# BoomClock.net
KiCad netlist of a schematic drawn in Altium Designer
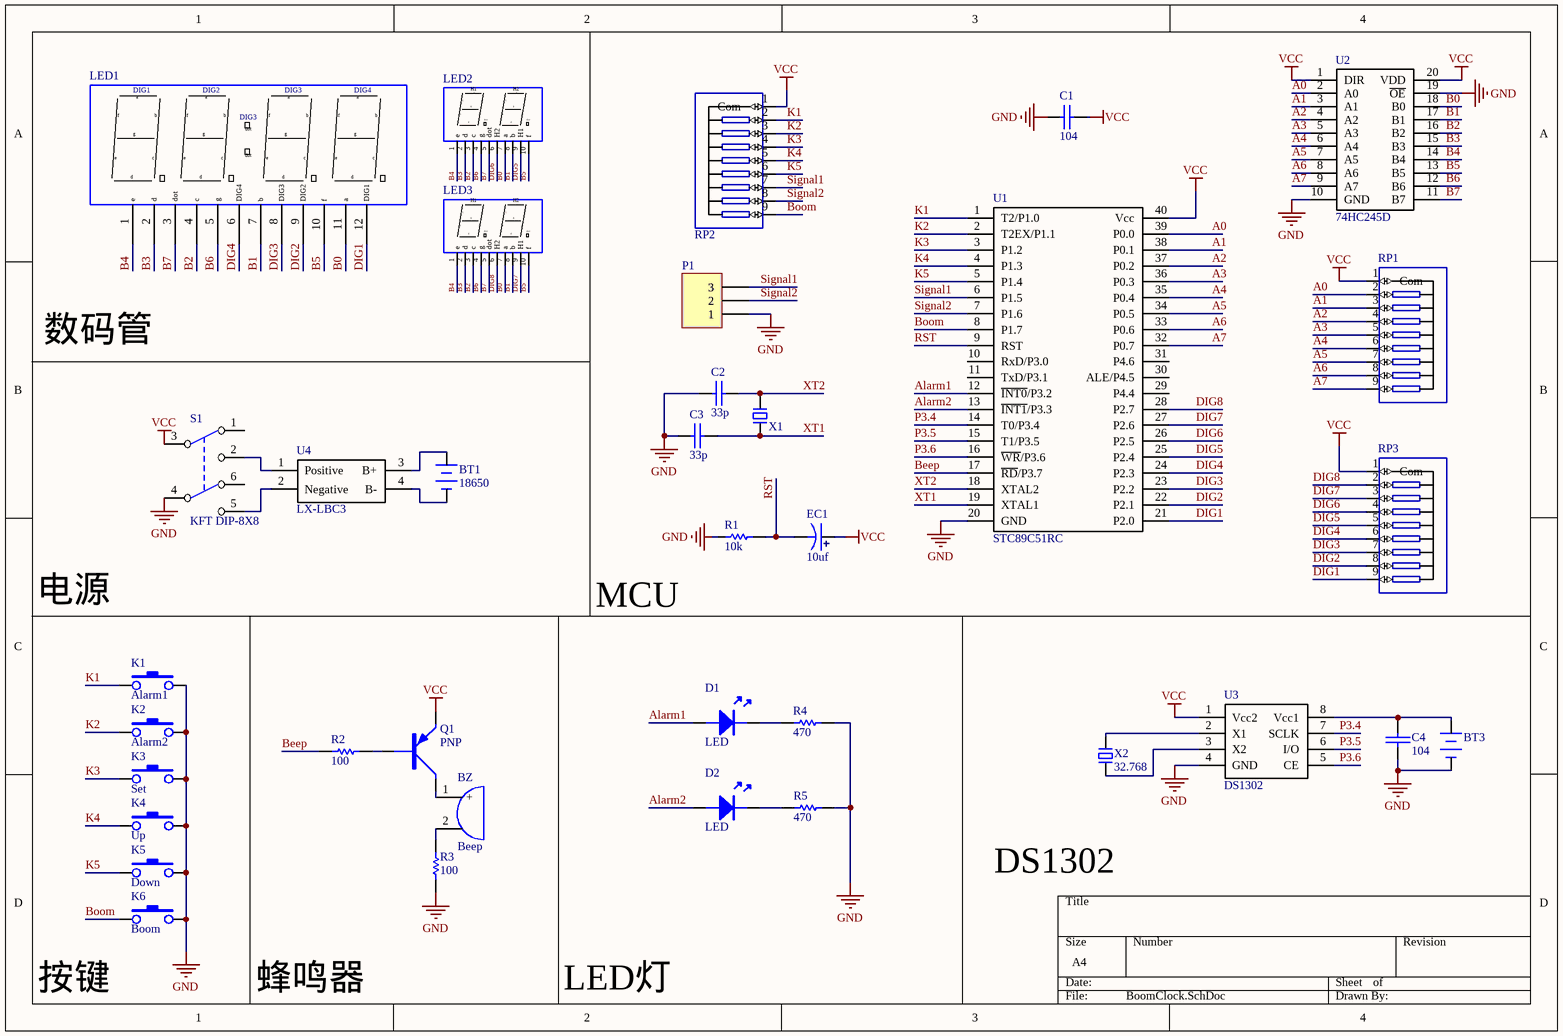
[diagram p0: BoomClock.SchDoc]

(export (version "E")
  (design (tool "Eeschema 10.0.6"))
  (components
    (comp (ref "BT1")
      (value "18650")
      (footprint "Battery_18650")
      (description "电池")
      (libsource (lib "BoomClock") (part "Battery"))
    )
    (comp (ref "BT3")
      (value "Battery")
      (footprint "Battery_CR2032")
      (description "电池")
      (libsource (lib "BoomClock") (part "Battery"))
    )
    (comp (ref "BZ")
      (value "Beep")
      (footprint "Beep")
      (description "蜂鸣器")
      (libsource (lib "BoomClock") (part "Beep"))
    )
    (comp (ref "C1")
      (value "104")
      (footprint "RAD-0.1")
      (description "无极性电容")
      (libsource (lib "BoomClock") (part "CAP"))
    )
    (comp (ref "C2")
      (value "33p")
      (footprint "RAD-0.1")
      (description "无极性电容")
      (libsource (lib "BoomClock") (part "CAP"))
    )
    (comp (ref "C3")
      (value "33p")
      (footprint "RAD-0.1")
      (description "无极性电容")
      (libsource (lib "BoomClock") (part "CAP"))
    )
    (comp (ref "C4")
      (value "104")
      (footprint "RAD-0.1")
      (description "无极性电容")
      (libsource (lib "BoomClock") (part "CAP"))
    )
    (comp (ref "D1") (value "LED") (footprint "LED5-YEL") (libsource (lib "BoomClock") (part "LED")))
    (comp (ref "D2") (value "LED") (footprint "LED5-BLUE") (libsource (lib "BoomClock") (part "LED")))
    (comp (ref "EC1")
      (value "10uf")
      (footprint "DIP-EC1.5X4X8")
      (description "直插电解电容")
      (libsource (lib "BoomClock") (part "DIP_ECAP"))
    )
    (comp (ref "K1")
      (value "Alarm1")
      (footprint "DIP-6X6X5")
      (description "按动开关")
      (libsource (lib "BoomClock") (part "KEY"))
    )
    (comp (ref "K2")
      (value "Alarm2")
      (footprint "DIP-6X6X5")
      (description "按动开关")
      (libsource (lib "BoomClock") (part "KEY"))
    )
    (comp (ref "K3")
      (value "Set")
      (footprint "DIP-6X6X5")
      (description "按动开关")
      (libsource (lib "BoomClock") (part "KEY"))
    )
    (comp (ref "K4")
      (value "Up")
      (footprint "DIP-6X6X5")
      (description "按动开关")
      (libsource (lib "BoomClock") (part "KEY"))
    )
    (comp (ref "K5")
      (value "Down")
      (footprint "DIP-6X6X5")
      (description "按动开关")
      (libsource (lib "BoomClock") (part "KEY"))
    )
    (comp (ref "K6")
      (value "Boom")
      (footprint "DIP-12X12X8")
      (description "按动开关")
      (libsource (lib "BoomClock") (part "KEY"))
    )
    (comp (ref "LED1")
      (value "Digital_4_time")
      (footprint "Digital_4_time")
      (description "四位时间数码管")
      (libsource (lib "BoomClock") (part "Digital_4_time"))
    )
    (comp (ref "LED2")
      (value "Digital_2")
      (footprint "Digital_2")
      (description "二位数码管")
      (libsource (lib "BoomClock") (part "Digital_2"))
    )
    (comp (ref "LED3")
      (value "Digital_2")
      (footprint "Digital_2")
      (description "二位数码管")
      (libsource (lib "BoomClock") (part "Digital_2"))
    )
    (comp (ref "P1")
      (value "Header 3")
      (footprint "HDR1X3")
      (description "Header, 3-Pin")
      (fields (field (name "PUBLISHER") "Altium Limited"))
      (libsource (lib "Miscellaneous Connectors") (part "Header 3"))
    )
    (comp (ref "Q1")
      (value "PNP")
      (footprint "SOT-23")
      (description "PNP三极管")
      (libsource (lib "BoomClock") (part "PNP"))
    )
    (comp (ref "R1")
      (value "10k")
      (footprint "0805R")
      (description "电阻")
      (libsource (lib "BoomClock") (part "RES"))
    )
    (comp (ref "R2")
      (value "100")
      (footprint "0805R")
      (description "电阻")
      (libsource (lib "BoomClock") (part "RES"))
    )
    (comp (ref "R3")
      (value "100")
      (footprint "0805R")
      (description "电阻")
      (libsource (lib "BoomClock") (part "RES"))
    )
    (comp (ref "R4")
      (value "470")
      (footprint "AXIAL0.4")
      (description "电阻")
      (libsource (lib "BoomClock") (part "RES"))
    )
    (comp (ref "R5")
      (value "470")
      (footprint "AXIAL0.4")
      (description "电阻")
      (libsource (lib "BoomClock") (part "RES"))
    )
    (comp (ref "RP1")
      (value "RES_PACK9")
      (footprint "A09R")
      (description "排阻")
      (libsource (lib "BoomClock") (part "RES_PACK9"))
    )
    (comp (ref "RP2")
      (value "RES_PACK9")
      (footprint "A09R")
      (description "排阻")
      (libsource (lib "BoomClock") (part "RES_PACK9"))
    )
    (comp (ref "RP3")
      (value "RES_PACK9")
      (footprint "A09R")
      (description "排阻")
      (libsource (lib "BoomClock") (part "RES_PACK9"))
    )
    (comp (ref "S1")
      (value "KFT DIP-8X8")
      (footprint "KFT DIP-8X8")
      (libsource (lib "BoomClock") (part "KFT DIP-8X8"))
    )
    (comp (ref "U1")
      (value "STC89C51RC")
      (footprint "DIP40")
      (libsource (lib "BoomClock") (part "STC89C51RC"))
    )
    (comp (ref "U2") (value "74HC245D") (footprint "SOP20") (libsource (lib "BoomClock") (part "74HC245D")))
    (comp (ref "U3") (value "DS1302") (footprint "DIP8") (libsource (lib "BoomClock") (part "DS1302")))
    (comp (ref "U4")
      (value "LX-LBC3")
      (footprint "LX-LBC3")
      (description "电源模块")
      (libsource (lib "BoomClock") (part "LX-LBC3"))
    )
    (comp (ref "X1")
      (value "XTAL-2P")
      (footprint "OSC HC-49S")
      (description "2脚无源脚晶振")
      (libsource (lib "BoomClock") (part "XTAL-2P"))
    )
    (comp (ref "X2")
      (value "32.768")
      (footprint "OSC-2x6-WI-A")
      (description "2脚无源脚晶振")
      (libsource (lib "BoomClock") (part "XTAL-2P"))
    )
  )
  (nets
    (net (code "1") (name "/A0") (class "Default")
      (node (ref "RP1") (pin "2") (pinfunction "2_2") (pintype "bidirectional"))
      (node (ref "U1") (pin "39") (pinfunction "P0.0_39") (pintype "passive"))
      (node (ref "U2") (pin "2") (pinfunction "A0_2") (pintype "passive"))
    )
    (net (code "2") (name "/A1") (class "Default")
      (node (ref "RP1") (pin "3") (pinfunction "3_3") (pintype "bidirectional"))
      (node (ref "U1") (pin "38") (pinfunction "P0.1_38") (pintype "passive"))
      (node (ref "U2") (pin "3") (pinfunction "A1_3") (pintype "passive"))
    )
    (net (code "3") (name "/A2") (class "Default")
      (node (ref "RP1") (pin "4") (pinfunction "4_4") (pintype "bidirectional"))
      (node (ref "U1") (pin "37") (pinfunction "P0.2_37") (pintype "passive"))
      (node (ref "U2") (pin "4") (pinfunction "A2_4") (pintype "passive"))
    )
    (net (code "4") (name "/A3") (class "Default")
      (node (ref "RP1") (pin "5") (pinfunction "5_5") (pintype "bidirectional"))
      (node (ref "U1") (pin "36") (pinfunction "P0.3_36") (pintype "passive"))
      (node (ref "U2") (pin "5") (pinfunction "A3_5") (pintype "passive"))
    )
    (net (code "5") (name "/A4") (class "Default")
      (node (ref "RP1") (pin "6") (pinfunction "6_6") (pintype "bidirectional"))
      (node (ref "U1") (pin "35") (pinfunction "P0.4_35") (pintype "passive"))
      (node (ref "U2") (pin "6") (pinfunction "A4_6") (pintype "passive"))
    )
    (net (code "6") (name "/A5") (class "Default")
      (node (ref "RP1") (pin "7") (pinfunction "7_7") (pintype "bidirectional"))
      (node (ref "U1") (pin "34") (pinfunction "P0.5_34") (pintype "passive"))
      (node (ref "U2") (pin "7") (pinfunction "A5_7") (pintype "passive"))
    )
    (net (code "7") (name "/A6") (class "Default")
      (node (ref "RP1") (pin "8") (pinfunction "8_8") (pintype "bidirectional"))
      (node (ref "U1") (pin "33") (pinfunction "P0.6_33") (pintype "passive"))
      (node (ref "U2") (pin "8") (pinfunction "A6_8") (pintype "passive"))
    )
    (net (code "8") (name "/A7") (class "Default")
      (node (ref "RP1") (pin "9") (pinfunction "9_9") (pintype "bidirectional"))
      (node (ref "U1") (pin "32") (pinfunction "P0.7_32") (pintype "passive"))
      (node (ref "U2") (pin "9") (pinfunction "A7_9") (pintype "passive"))
    )
    (net (code "9") (name "/Alarm1") (class "Default")
      (node (ref "D1") (pin "A") (pinfunction "A_A") (pintype "passive"))
      (node (ref "U1") (pin "12") (pinfunction "~{INT0}/P3.2_12") (pintype "passive"))
    )
    (net (code "10") (name "/Alarm2") (class "Default")
      (node (ref "D2") (pin "A") (pinfunction "A_A") (pintype "passive"))
      (node (ref "U1") (pin "13") (pinfunction "~{INT1}/P3.3_13") (pintype "passive"))
    )
    (net (code "11") (name "/B0") (class "Default")
      (node (ref "LED1") (pin "11") (pinfunction "a_11") (pintype "passive"))
      (node (ref "LED2") (pin "7") (pinfunction "a_7") (pintype "passive"))
      (node (ref "LED3") (pin "7") (pinfunction "a_7") (pintype "passive"))
      (node (ref "U2") (pin "18") (pinfunction "B0_18") (pintype "passive"))
    )
    (net (code "12") (name "/B1") (class "Default")
      (node (ref "LED1") (pin "7") (pinfunction "b_7") (pintype "passive"))
      (node (ref "LED2") (pin "8") (pinfunction "b_8") (pintype "passive"))
      (node (ref "LED3") (pin "8") (pinfunction "b_8") (pintype "passive"))
      (node (ref "U2") (pin "17") (pinfunction "B1_17") (pintype "passive"))
    )
    (net (code "13") (name "/B2") (class "Default")
      (node (ref "LED1") (pin "4") (pinfunction "c_4") (pintype "passive"))
      (node (ref "LED2") (pin "3") (pinfunction "c_3") (pintype "passive"))
      (node (ref "LED3") (pin "3") (pinfunction "c_3") (pintype "passive"))
      (node (ref "U2") (pin "16") (pinfunction "B2_16") (pintype "passive"))
    )
    (net (code "14") (name "/B3") (class "Default")
      (node (ref "LED1") (pin "2") (pinfunction "d_2") (pintype "passive"))
      (node (ref "LED2") (pin "2") (pinfunction "d_2") (pintype "passive"))
      (node (ref "LED3") (pin "2") (pinfunction "d_2") (pintype "passive"))
      (node (ref "U2") (pin "15") (pinfunction "B3_15") (pintype "passive"))
    )
    (net (code "15") (name "/B4") (class "Default")
      (node (ref "LED1") (pin "1") (pinfunction "e_1") (pintype "passive"))
      (node (ref "LED2") (pin "1") (pinfunction "e_1") (pintype "passive"))
      (node (ref "LED3") (pin "1") (pinfunction "e_1") (pintype "passive"))
      (node (ref "U2") (pin "14") (pinfunction "B4_14") (pintype "passive"))
    )
    (net (code "16") (name "/B5") (class "Default")
      (node (ref "LED1") (pin "10") (pinfunction "f_10") (pintype "passive"))
      (node (ref "LED2") (pin "10") (pinfunction "f_10") (pintype "passive"))
      (node (ref "LED3") (pin "10") (pinfunction "f_10") (pintype "passive"))
      (node (ref "U2") (pin "13") (pinfunction "B5_13") (pintype "passive"))
    )
    (net (code "17") (name "/B6") (class "Default")
      (node (ref "LED1") (pin "5") (pinfunction "g_5") (pintype "passive"))
      (node (ref "LED2") (pin "4") (pinfunction "g_4") (pintype "passive"))
      (node (ref "LED3") (pin "4") (pinfunction "g_4") (pintype "passive"))
      (node (ref "U2") (pin "12") (pinfunction "B6_12") (pintype "passive"))
    )
    (net (code "18") (name "/B7") (class "Default")
      (node (ref "LED1") (pin "3") (pinfunction "dot_3") (pintype "passive"))
      (node (ref "LED2") (pin "5") (pinfunction "dot_5") (pintype "passive"))
      (node (ref "LED3") (pin "5") (pinfunction "dot_5") (pintype "passive"))
      (node (ref "U2") (pin "11") (pinfunction "B7_11") (pintype "passive"))
    )
    (net (code "19") (name "/Beep") (class "Default")
      (node (ref "R2") (pin "1") (pinfunction "1_1") (pintype "passive"))
      (node (ref "U1") (pin "17") (pinfunction "~{RD}/P3.7_17") (pintype "passive"))
    )
    (net (code "20") (name "/Boom") (class "Default")
      (node (ref "K6") (pin "1") (pinfunction "1_1") (pintype "passive"))
      (node (ref "RP2") (pin "9") (pinfunction "9_9") (pintype "bidirectional"))
      (node (ref "U1") (pin "8") (pinfunction "P1.7_8") (pintype "passive"))
    )
    (net (code "21") (name "/DIG1") (class "Default")
      (node (ref "LED1") (pin "12") (pinfunction "DIG1_12") (pintype "passive"))
      (node (ref "RP3") (pin "9") (pinfunction "9_9") (pintype "bidirectional"))
      (node (ref "U1") (pin "21") (pinfunction "P2.0_21") (pintype "passive"))
    )
    (net (code "22") (name "/DIG2") (class "Default")
      (node (ref "LED1") (pin "9") (pinfunction "DIG2_9") (pintype "passive"))
      (node (ref "RP3") (pin "8") (pinfunction "8_8") (pintype "bidirectional"))
      (node (ref "U1") (pin "22") (pinfunction "P2.1_22") (pintype "passive"))
    )
    (net (code "23") (name "/DIG3") (class "Default")
      (node (ref "LED1") (pin "8") (pinfunction "DIG3_8") (pintype "passive"))
      (node (ref "RP3") (pin "7") (pinfunction "7_7") (pintype "bidirectional"))
      (node (ref "U1") (pin "23") (pinfunction "P2.2_23") (pintype "passive"))
    )
    (net (code "24") (name "/DIG4") (class "Default")
      (node (ref "LED1") (pin "6") (pinfunction "DIG4_6") (pintype "passive"))
      (node (ref "RP3") (pin "6") (pinfunction "6_6") (pintype "bidirectional"))
      (node (ref "U1") (pin "24") (pinfunction "P2.3_24") (pintype "passive"))
    )
    (net (code "25") (name "/DIG5") (class "Default")
      (node (ref "LED2") (pin "9") (pinfunction "H1_9") (pintype "passive"))
      (node (ref "RP3") (pin "5") (pinfunction "5_5") (pintype "bidirectional"))
      (node (ref "U1") (pin "25") (pinfunction "P2.4_25") (pintype "passive"))
    )
    (net (code "26") (name "/DIG6") (class "Default")
      (node (ref "LED2") (pin "6") (pinfunction "H2_6") (pintype "passive"))
      (node (ref "RP3") (pin "4") (pinfunction "4_4") (pintype "bidirectional"))
      (node (ref "U1") (pin "26") (pinfunction "P2.5_26") (pintype "passive"))
    )
    (net (code "27") (name "/DIG7") (class "Default")
      (node (ref "LED3") (pin "9") (pinfunction "H1_9") (pintype "passive"))
      (node (ref "RP3") (pin "3") (pinfunction "3_3") (pintype "bidirectional"))
      (node (ref "U1") (pin "27") (pinfunction "P2.6_27") (pintype "passive"))
    )
    (net (code "28") (name "/DIG8") (class "Default")
      (node (ref "LED3") (pin "6") (pinfunction "H2_6") (pintype "passive"))
      (node (ref "RP3") (pin "2") (pinfunction "2_2") (pintype "bidirectional"))
      (node (ref "U1") (pin "28") (pinfunction "P2.7_28") (pintype "passive"))
    )
    (net (code "29") (name "/K1") (class "Default")
      (node (ref "K1") (pin "1") (pinfunction "1_1") (pintype "passive"))
      (node (ref "RP2") (pin "2") (pinfunction "2_2") (pintype "bidirectional"))
      (node (ref "U1") (pin "1") (pinfunction "T2/P1.0_1") (pintype "passive"))
    )
    (net (code "30") (name "/K2") (class "Default")
      (node (ref "K2") (pin "1") (pinfunction "1_1") (pintype "passive"))
      (node (ref "RP2") (pin "3") (pinfunction "3_3") (pintype "bidirectional"))
      (node (ref "U1") (pin "2") (pinfunction "T2EX/P1.1_2") (pintype "passive"))
    )
    (net (code "31") (name "/K3") (class "Default")
      (node (ref "K3") (pin "1") (pinfunction "1_1") (pintype "passive"))
      (node (ref "RP2") (pin "4") (pinfunction "4_4") (pintype "bidirectional"))
      (node (ref "U1") (pin "3") (pinfunction "P1.2_3") (pintype "passive"))
    )
    (net (code "32") (name "/K4") (class "Default")
      (node (ref "K4") (pin "1") (pinfunction "1_1") (pintype "passive"))
      (node (ref "RP2") (pin "5") (pinfunction "5_5") (pintype "bidirectional"))
      (node (ref "U1") (pin "4") (pinfunction "P1.3_4") (pintype "passive"))
    )
    (net (code "33") (name "/K5") (class "Default")
      (node (ref "K5") (pin "1") (pinfunction "1_1") (pintype "passive"))
      (node (ref "RP2") (pin "6") (pinfunction "6_6") (pintype "bidirectional"))
      (node (ref "U1") (pin "5") (pinfunction "P1.4_5") (pintype "passive"))
    )
    (net (code "34") (name "/P3.4") (class "Default")
      (node (ref "U1") (pin "14") (pinfunction "T0/P3.4_14") (pintype "passive"))
      (node (ref "U3") (pin "7") (pinfunction "SCLK_7") (pintype "passive"))
    )
    (net (code "35") (name "/P3.5") (class "Default")
      (node (ref "U1") (pin "15") (pinfunction "T1/P3.5_15") (pintype "passive"))
      (node (ref "U3") (pin "6") (pinfunction "I/O_6") (pintype "passive"))
    )
    (net (code "36") (name "/P3.6") (class "Default")
      (node (ref "U1") (pin "16") (pinfunction "~{WR}/P3.6_16") (pintype "passive"))
      (node (ref "U3") (pin "5") (pinfunction "CE_5") (pintype "passive"))
    )
    (net (code "37") (name "/RST") (class "Default")
      (node (ref "EC1") (pin "2") (pinfunction "2_2") (pintype "passive"))
      (node (ref "R1") (pin "2") (pinfunction "2_2") (pintype "passive"))
      (node (ref "U1") (pin "9") (pinfunction "RST_9") (pintype "passive"))
    )
    (net (code "38") (name "/Signal1") (class "Default")
      (node (ref "P1") (pin "3") (pinfunction "3_3") (pintype "passive"))
      (node (ref "RP2") (pin "7") (pinfunction "7_7") (pintype "bidirectional"))
      (node (ref "U1") (pin "6") (pinfunction "P1.5_6") (pintype "passive"))
    )
    (net (code "39") (name "/Signal2") (class "Default")
      (node (ref "P1") (pin "2") (pinfunction "2_2") (pintype "passive"))
      (node (ref "RP2") (pin "8") (pinfunction "8_8") (pintype "bidirectional"))
      (node (ref "U1") (pin "7") (pinfunction "P1.6_7") (pintype "passive"))
    )
    (net (code "40") (name "/XT1") (class "Default")
      (node (ref "C3") (pin "2") (pinfunction "2_2") (pintype "passive"))
      (node (ref "U1") (pin "19") (pinfunction "XTAL1_19") (pintype "passive"))
      (node (ref "X1") (pin "1") (pinfunction "1_1") (pintype "passive"))
    )
    (net (code "41") (name "/XT2") (class "Default")
      (node (ref "C2") (pin "2") (pinfunction "2_2") (pintype "passive"))
      (node (ref "U1") (pin "18") (pinfunction "XTAL2_18") (pintype "passive"))
      (node (ref "X1") (pin "2") (pinfunction "2_2") (pintype "passive"))
    )
    (net (code "42") (name "GND") (class "Default")
      (node (ref "BT3") (pin "2") (pinfunction "Negative_2") (pintype "passive"))
      (node (ref "C1") (pin "1") (pinfunction "1_1") (pintype "passive"))
      (node (ref "C2") (pin "1") (pinfunction "1_1") (pintype "passive"))
      (node (ref "C3") (pin "1") (pinfunction "1_1") (pintype "passive"))
      (node (ref "C4") (pin "1") (pinfunction "1_1") (pintype "passive"))
      (node (ref "K1") (pin "2") (pinfunction "2_2") (pintype "passive"))
      (node (ref "K2") (pin "2") (pinfunction "2_2") (pintype "passive"))
      (node (ref "K3") (pin "2") (pinfunction "2_2") (pintype "passive"))
      (node (ref "K4") (pin "2") (pinfunction "2_2") (pintype "passive"))
      (node (ref "K5") (pin "2") (pinfunction "2_2") (pintype "passive"))
      (node (ref "K6") (pin "2") (pinfunction "2_2") (pintype "passive"))
      (node (ref "P1") (pin "1") (pinfunction "1_1") (pintype "passive"))
      (node (ref "R1") (pin "1") (pinfunction "1_1") (pintype "passive"))
      (node (ref "R3") (pin "1") (pinfunction "1_1") (pintype "passive"))
      (node (ref "R4") (pin "2") (pinfunction "2_2") (pintype "passive"))
      (node (ref "R5") (pin "2") (pinfunction "2_2") (pintype "passive"))
      (node (ref "S1") (pin "4") (pinfunction "4_4") (pintype "passive"))
      (node (ref "U1") (pin "20") (pinfunction "GND_20") (pintype "passive"))
      (node (ref "U2") (pin "10") (pinfunction "GND_10") (pintype "passive"))
      (node (ref "U2") (pin "19") (pinfunction "~{OE}_19") (pintype "passive"))
      (node (ref "U3") (pin "4") (pinfunction "GND_4") (pintype "passive"))
    )
    (net (code "43") (name "Net-(BT1-Negative)") (class "Default")
      (node (ref "BT1") (pin "2") (pinfunction "Negative_2") (pintype "passive"))
      (node (ref "U4") (pin "4") (pinfunction "B-_4") (pintype "passive"))
    )
    (net (code "44") (name "Net-(BT1-Positive)") (class "Default")
      (node (ref "BT1") (pin "1") (pinfunction "Positive_1") (pintype "passive"))
      (node (ref "U4") (pin "3") (pinfunction "B+_3") (pintype "passive"))
    )
    (net (code "45") (name "Net-(BT3-Positive)") (class "Default")
      (node (ref "BT3") (pin "1") (pinfunction "Positive_1") (pintype "passive"))
      (node (ref "C4") (pin "2") (pinfunction "2_2") (pintype "passive"))
      (node (ref "U3") (pin "8") (pinfunction "Vcc1_8") (pintype "passive"))
    )
    (net (code "46") (name "Net-(BZ-Pad1)") (class "Default")
      (node (ref "BZ") (pin "1") (pinfunction "1_1") (pintype "passive"))
      (node (ref "Q1") (pin "C") (pinfunction "C_C") (pintype "passive"))
    )
    (net (code "47") (name "Net-(BZ-Pad2)") (class "Default")
      (node (ref "BZ") (pin "2") (pinfunction "2_2") (pintype "passive"))
      (node (ref "R3") (pin "2") (pinfunction "2_2") (pintype "passive"))
    )
    (net (code "48") (name "Net-(D1-PadK)") (class "Default")
      (node (ref "D1") (pin "K") (pinfunction "K_K") (pintype "passive"))
      (node (ref "R4") (pin "1") (pinfunction "1_1") (pintype "passive"))
    )
    (net (code "49") (name "Net-(D2-PadK)") (class "Default")
      (node (ref "D2") (pin "K") (pinfunction "K_K") (pintype "passive"))
      (node (ref "R5") (pin "1") (pinfunction "1_1") (pintype "passive"))
    )
    (net (code "50") (name "Net-(Q1-PadB)") (class "Default")
      (node (ref "Q1") (pin "B") (pinfunction "B_B") (pintype "passive"))
      (node (ref "R2") (pin "2") (pinfunction "2_2") (pintype "passive"))
    )
    (net (code "51") (name "Net-(U3-X1)") (class "Default")
      (node (ref "U3") (pin "2") (pinfunction "X1_2") (pintype "passive"))
      (node (ref "X2") (pin "2") (pinfunction "2_2") (pintype "passive"))
    )
    (net (code "52") (name "Net-(U3-X2)") (class "Default")
      (node (ref "U3") (pin "3") (pinfunction "X2_3") (pintype "passive"))
      (node (ref "X2") (pin "1") (pinfunction "1_1") (pintype "passive"))
    )
    (net (code "53") (name "Net-(U4-Negative)") (class "Default")
      (node (ref "S1") (pin "5") (pinfunction "5_5") (pintype "passive"))
      (node (ref "U4") (pin "2") (pinfunction "Negative_2") (pintype "passive"))
    )
    (net (code "54") (name "Net-(U4-Positive)") (class "Default")
      (node (ref "S1") (pin "2") (pinfunction "2_2") (pintype "passive"))
      (node (ref "U4") (pin "1") (pinfunction "Positive_1") (pintype "passive"))
    )
    (net (code "55") (name "VCC") (class "Default")
      (node (ref "C1") (pin "2") (pinfunction "2_2") (pintype "passive"))
      (node (ref "EC1") (pin "1") (pinfunction "1_1") (pintype "passive"))
      (node (ref "Q1") (pin "E") (pinfunction "E_E") (pintype "passive"))
      (node (ref "RP1") (pin "1") (pinfunction "Com_1") (pintype "bidirectional"))
      (node (ref "RP2") (pin "1") (pinfunction "Com_1") (pintype "bidirectional"))
      (node (ref "RP3") (pin "1") (pinfunction "Com_1") (pintype "bidirectional"))
      (node (ref "S1") (pin "3") (pinfunction "3_3") (pintype "passive"))
      (node (ref "U1") (pin "40") (pinfunction "Vcc_40") (pintype "passive"))
      (node (ref "U2") (pin "1") (pinfunction "DIR_1") (pintype "passive"))
      (node (ref "U2") (pin "20") (pinfunction "VDD_20") (pintype "passive"))
      (node (ref "U3") (pin "1") (pinfunction "Vcc2_1") (pintype "passive"))
    )
    (net (code "56") (name "unconnected-(S1-Pad1)") (class "Default")
      (node (ref "S1") (pin "1") (pinfunction "1_1") (pintype "passive"))
    )
    (net (code "57") (name "unconnected-(S1-Pad6)") (class "Default")
      (node (ref "S1") (pin "6") (pinfunction "6_6") (pintype "passive"))
    )
    (net (code "58") (name "unconnected-(U1-ALE{slash}P4.5-Pad30)") (class "Default")
      (node (ref "U1") (pin "30") (pinfunction "ALE/P4.5_30") (pintype "passive"))
    )
    (net (code "59") (name "unconnected-(U1-P4.4-Pad29)") (class "Default")
      (node (ref "U1") (pin "29") (pinfunction "P4.4_29") (pintype "passive"))
    )
    (net (code "60") (name "unconnected-(U1-P4.6-Pad31)") (class "Default")
      (node (ref "U1") (pin "31") (pinfunction "P4.6_31") (pintype "passive"))
    )
    (net (code "61") (name "unconnected-(U1-RxD{slash}P3.0-Pad10)") (class "Default")
      (node (ref "U1") (pin "10") (pinfunction "RxD/P3.0_10") (pintype "passive"))
    )
    (net (code "62") (name "unconnected-(U1-TxD{slash}P3.1-Pad11)") (class "Default")
      (node (ref "U1") (pin "11") (pinfunction "TxD/P3.1_11") (pintype "passive"))
    )
  )
)
